# mp3431-led-boost-driver-17mm-mk-1_0_0.net
KiCad netlist of a schematic drawn in EAGLE
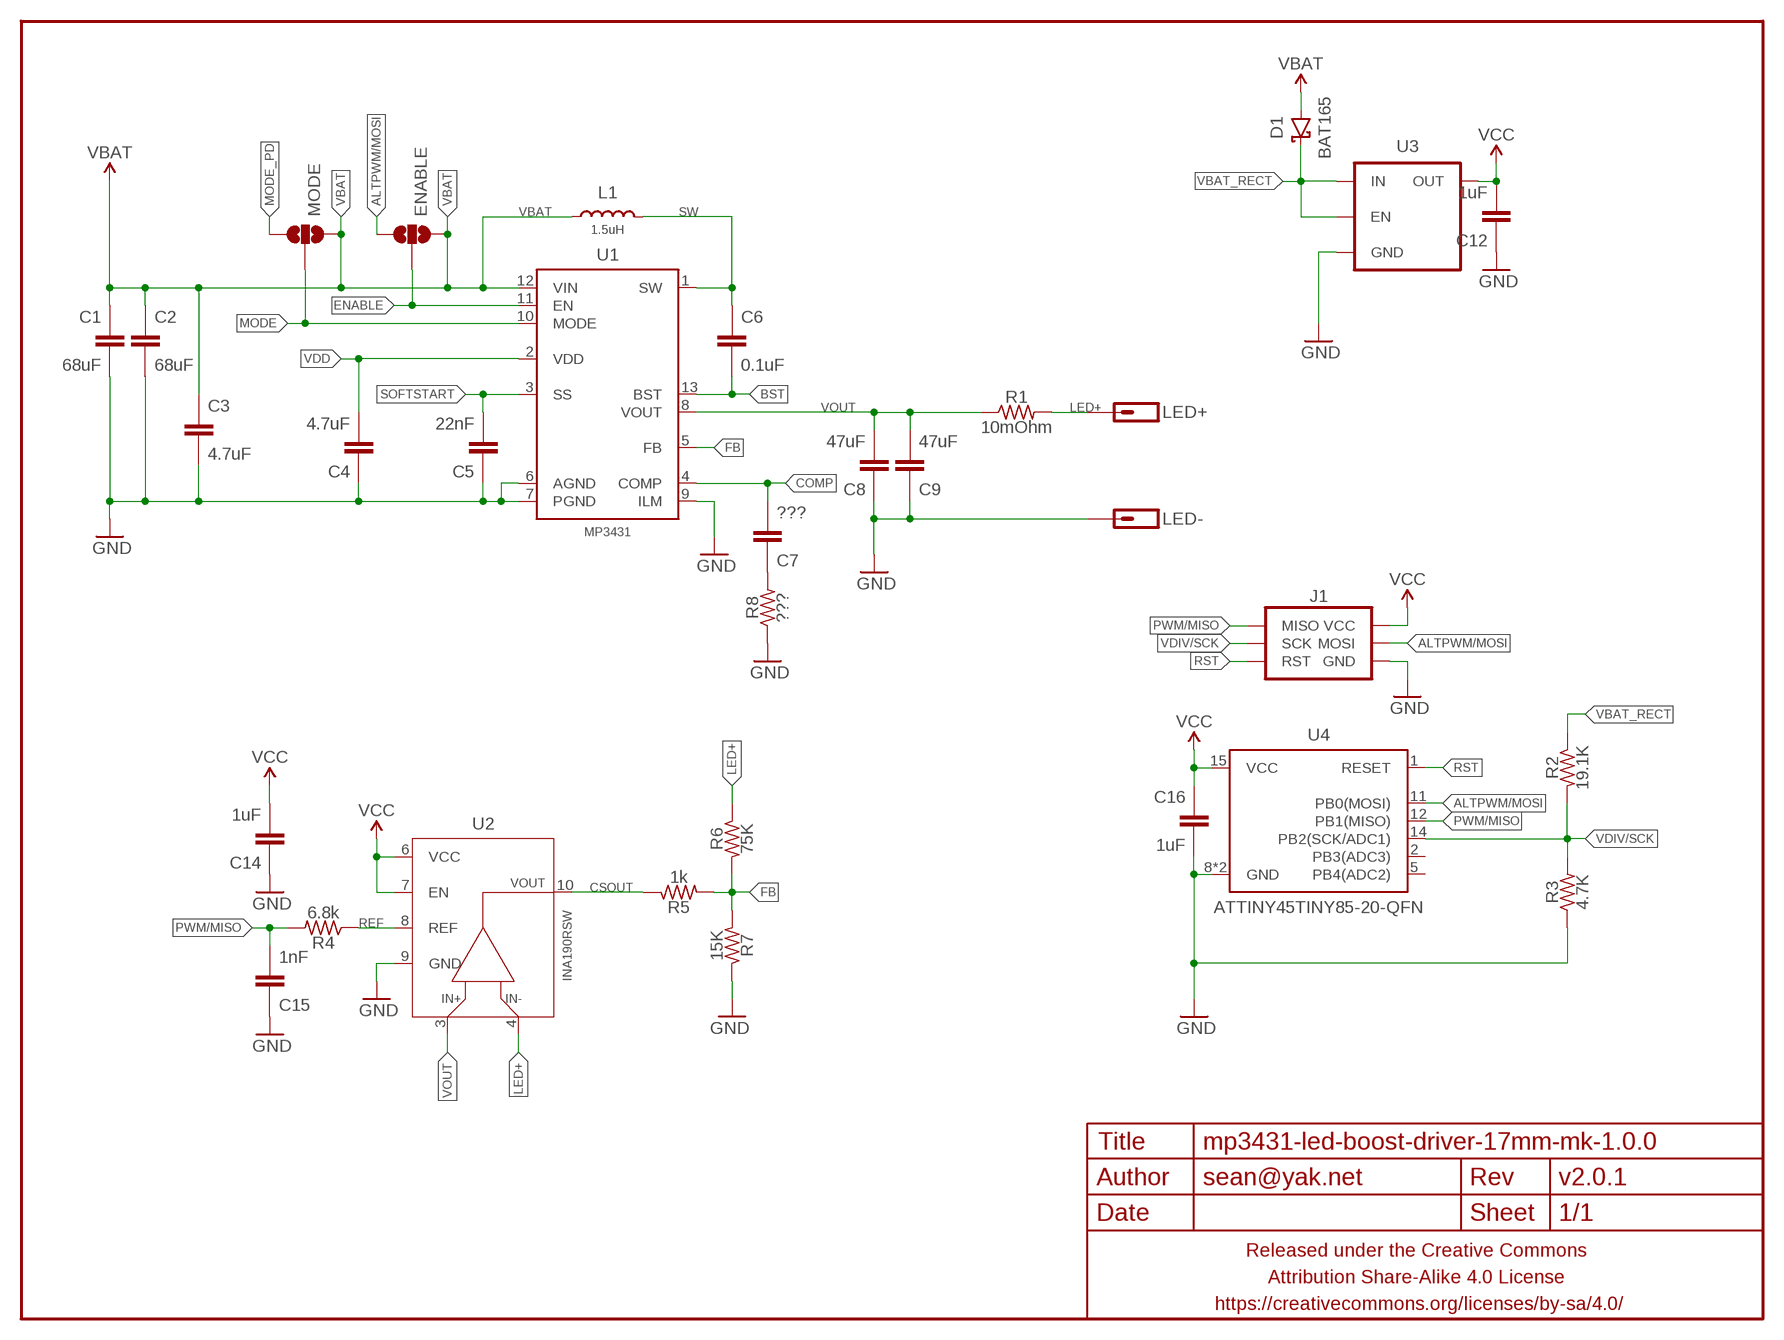
[diagram p0: schematic, sheet 1]

(export (version "E")
  (design (tool "Eeschema 10.0.6"))
  (components
    (comp (ref "C1")
      (value "68uF")
      (footprint "eagle-import:C1206")
      (libsource (lib "eagle-import") (part "CAPACITOR-CERAMICC1206"))
    )
    (comp (ref "C2")
      (value "68uF")
      (footprint "eagle-import:C1206")
      (libsource (lib "eagle-import") (part "CAPACITOR-CERAMICC1206"))
    )
    (comp (ref "C3")
      (value "4.7uF")
      (footprint "eagle-import:C0402")
      (libsource (lib "eagle-import") (part "CAPACITOR-CERAMICC0402"))
    )
    (comp (ref "C4")
      (value "4.7uF")
      (footprint "eagle-import:C0402")
      (libsource (lib "eagle-import") (part "CAPACITOR-CERAMICC0402"))
    )
    (comp (ref "C5")
      (value "22nF")
      (footprint "eagle-import:C0402")
      (libsource (lib "eagle-import") (part "CAPACITOR-CERAMICC0402"))
    )
    (comp (ref "C6")
      (value "0.1uF")
      (footprint "eagle-import:C0402")
      (libsource (lib "eagle-import") (part "CAPACITOR-CERAMICC0402"))
    )
    (comp (ref "C7")
      (value "???")
      (footprint "eagle-import:C0402")
      (libsource (lib "eagle-import") (part "CAPACITOR-CERAMICC0402"))
    )
    (comp (ref "C8")
      (value "47uF")
      (footprint "eagle-import:C1206")
      (libsource (lib "eagle-import") (part "CAPACITOR-CERAMICC1206"))
    )
    (comp (ref "C9")
      (value "47uF")
      (footprint "eagle-import:C1206")
      (libsource (lib "eagle-import") (part "CAPACITOR-CERAMICC1206"))
    )
    (comp (ref "C12")
      (value "1uF")
      (footprint "eagle-import:C0402")
      (libsource (lib "eagle-import") (part "CAPACITOR-CERAMICC0402"))
    )
    (comp (ref "C14")
      (value "1uF")
      (footprint "eagle-import:C0402")
      (libsource (lib "eagle-import") (part "CAPACITOR-CERAMICC0402"))
    )
    (comp (ref "C15")
      (value "1nF")
      (footprint "eagle-import:C0402")
      (libsource (lib "eagle-import") (part "CAPACITOR-CERAMICC0402"))
    )
    (comp (ref "C16")
      (value "1uF")
      (footprint "eagle-import:C0402")
      (libsource (lib "eagle-import") (part "CAPACITOR-CERAMICC0402"))
    )
    (comp (ref "D1")
      (value "BAT165")
      (footprint "eagle-import:SOD323-SCHOTTKY")
      (libsource (lib "eagle-import") (part "DIODE-SCHOTTKYSOD323"))
    )
    (comp (ref "ENABLE")
      (value "JUMPER-PAD-3-NOSMALL_BOX_SILK")
      (footprint "eagle-import:PAD-JUMPER-3-NO_YES_SILK_SMALL_BOX")
      (libsource (lib "eagle-import") (part "JUMPER-PAD-3-NOSMALL_BOX_SILK"))
    )
    (comp (ref "FRAME1")
      (value "FRAME-LETTERNO_PACKAGE")
      (footprint "eagle-import:DUMMY")
      (fields
        (field (name "DESIGNER") "sean@yak.net")
        (field (name "VERSION") "v2.0.1")
        (field (name "DESIGNER_1") "sean@yak.net")
        (field (name "VERSION_1") "v2.0.1")
      )
      (libsource (lib "eagle-import") (part "FRAME-LETTERNO_PACKAGE"))
    )
    (comp (ref "J1")
      (value "AVR_SPI_PRG_6SMD-1.27MM")
      (footprint "eagle-import:2X3-1.27MM-SMD")
      (libsource (lib "eagle-import") (part "AVR_SPI_PRG_6SMD-1.27MM"))
    )
    (comp (ref "L1")
      (value "1.5uH")
      (footprint "eagle-import:XAR7030")
      (libsource (lib "eagle-import") (part "INDUCTORXAR7030"))
    )
    (comp (ref "LED+")
      (value "M01SMD-1.6MMX3.2MM")
      (footprint "eagle-import:1X01-SMD-1.6MMX3.2MM")
      (libsource (lib "eagle-import") (part "M01SMD-1.6MMX3.2MM"))
    )
    (comp (ref "LED-")
      (value "M01SMD-1.6MMX3.2MM")
      (footprint "eagle-import:1X01-SMD-1.6MMX3.2MM")
      (libsource (lib "eagle-import") (part "M01SMD-1.6MMX3.2MM"))
    )
    (comp (ref "MODE")
      (value "JUMPER-PAD-3-NOSMALL_BOX_SILK")
      (footprint "eagle-import:PAD-JUMPER-3-NO_YES_SILK_SMALL_BOX")
      (libsource (lib "eagle-import") (part "JUMPER-PAD-3-NOSMALL_BOX_SILK"))
    )
    (comp (ref "R1")
      (value "10mOhm")
      (footprint "eagle-import:R1206")
      (libsource (lib "eagle-import") (part "RESISTORR1206"))
    )
    (comp (ref "R2")
      (value "19.1K")
      (footprint "eagle-import:R0402")
      (libsource (lib "eagle-import") (part "RESISTORR0402"))
    )
    (comp (ref "R3")
      (value "4.7K")
      (footprint "eagle-import:R0402")
      (libsource (lib "eagle-import") (part "RESISTORR0402"))
    )
    (comp (ref "R4")
      (value "6.8k")
      (footprint "eagle-import:R0402")
      (libsource (lib "eagle-import") (part "RESISTORR0402"))
    )
    (comp (ref "R5")
      (value "1k")
      (footprint "eagle-import:R0402")
      (libsource (lib "eagle-import") (part "RESISTORR0402"))
    )
    (comp (ref "R6")
      (value "75K")
      (footprint "eagle-import:R0402")
      (libsource (lib "eagle-import") (part "RESISTORR0402"))
    )
    (comp (ref "R7")
      (value "15K")
      (footprint "eagle-import:R0402")
      (libsource (lib "eagle-import") (part "RESISTORR0402"))
    )
    (comp (ref "R8")
      (value "???")
      (footprint "eagle-import:R0402")
      (libsource (lib "eagle-import") (part "RESISTORR0402"))
    )
    (comp (ref "U1")
      (value "MP3431")
      (footprint "eagle-import:MP3431")
      (libsource (lib "eagle-import") (part "MP3431"))
    )
    (comp (ref "U2")
      (value "INA190RSW")
      (footprint "eagle-import:UQFN-10")
      (libsource (lib "eagle-import") (part "INA190RSW"))
    )
    (comp (ref "U3")
      (value "V_REG_ENTLV700")
      (footprint "eagle-import:SC70")
      (libsource (lib "eagle-import") (part "V_REG_ENTLV700"))
    )
    (comp (ref "U4")
      (value "ATTINY45TINY85-20-QFN")
      (footprint "eagle-import:QFN20")
      (libsource (lib "eagle-import") (part "ATTINY45TINY85-20-QFN"))
    )
  )
  (nets
    (net (code "1") (name "/CSOUT") (class "Default")
      (node (ref "R5") (pin "1") (pinfunction "1_1") (pintype "passive"))
      (node (ref "U2") (pin "10") (pinfunction "OUT_10") (pintype "bidirectional"))
    )
    (net (code "2") (name "/REF") (class "Default")
      (node (ref "R4") (pin "1") (pinfunction "1_1") (pintype "passive"))
      (node (ref "U2") (pin "8") (pinfunction "REF_8") (pintype "bidirectional"))
    )
    (net (code "3") (name "/SW") (class "Default")
      (node (ref "C6") (pin "1") (pinfunction "1_1") (pintype "passive"))
      (node (ref "L1") (pin "P$2") (pinfunction "2_P$2") (pintype "passive"))
      (node (ref "U1") (pin "1") (pinfunction "SW_1") (pintype "bidirectional"))
    )
    (net (code "4") (name "ALTPWM{slash}MOSI") (class "Default")
      (node (ref "ENABLE") (pin "3") (pinfunction "3_3") (pintype "passive"))
      (node (ref "J1") (pin "4") (pinfunction "MOSI_4") (pintype "passive"))
      (node (ref "U4") (pin "11") (pinfunction "PB0(MOSI)_11") (pintype "bidirectional"))
    )
    (net (code "5") (name "BST") (class "Default")
      (node (ref "C6") (pin "2") (pinfunction "2_2") (pintype "passive"))
      (node (ref "U1") (pin "13") (pinfunction "BST_13") (pintype "bidirectional"))
    )
    (net (code "6") (name "COMP") (class "Default")
      (node (ref "C7") (pin "2") (pinfunction "2_2") (pintype "passive"))
      (node (ref "U1") (pin "4") (pinfunction "COMP_4") (pintype "bidirectional"))
    )
    (net (code "7") (name "ENABLE") (class "Default")
      (node (ref "ENABLE") (pin "2") (pinfunction "2_2") (pintype "passive"))
      (node (ref "U1") (pin "11") (pinfunction "EN_11") (pintype "bidirectional"))
    )
    (net (code "8") (name "FB") (class "Default")
      (node (ref "R5") (pin "2") (pinfunction "2_2") (pintype "passive"))
      (node (ref "R6") (pin "2") (pinfunction "2_2") (pintype "passive"))
      (node (ref "R7") (pin "2") (pinfunction "2_2") (pintype "passive"))
      (node (ref "U1") (pin "5") (pinfunction "FB_5") (pintype "bidirectional"))
    )
    (net (code "9") (name "GND") (class "Default")
      (node (ref "C1") (pin "2") (pinfunction "2_2") (pintype "passive"))
      (node (ref "C12") (pin "1") (pinfunction "1_1") (pintype "passive"))
      (node (ref "C14") (pin "1") (pinfunction "1_1") (pintype "passive"))
      (node (ref "C15") (pin "1") (pinfunction "1_1") (pintype "passive"))
      (node (ref "C16") (pin "2") (pinfunction "2_2") (pintype "passive"))
      (node (ref "C2") (pin "2") (pinfunction "2_2") (pintype "passive"))
      (node (ref "C3") (pin "2") (pinfunction "2_2") (pintype "passive"))
      (node (ref "C4") (pin "1") (pinfunction "1_1") (pintype "passive"))
      (node (ref "C5") (pin "1") (pinfunction "1_1") (pintype "passive"))
      (node (ref "C8") (pin "1") (pinfunction "1_1") (pintype "passive"))
      (node (ref "C9") (pin "1") (pinfunction "1_1") (pintype "passive"))
      (node (ref "J1") (pin "6") (pinfunction "GND_6") (pintype "passive"))
      (node (ref "LED-") (pin "P$1") (pinfunction "1_P$1") (pintype "passive"))
      (node (ref "R3") (pin "1") (pinfunction "1_1") (pintype "passive"))
      (node (ref "R7") (pin "1") (pinfunction "1_1") (pintype "passive"))
      (node (ref "R8") (pin "1") (pinfunction "1_1") (pintype "passive"))
      (node (ref "U1") (pin "6") (pinfunction "AGND_6") (pintype "bidirectional"))
      (node (ref "U1") (pin "7") (pinfunction "PGND_7") (pintype "bidirectional"))
      (node (ref "U1") (pin "9") (pinfunction "ILM_9") (pintype "bidirectional"))
      (node (ref "U2") (pin "9") (pinfunction "GND_9") (pintype "bidirectional"))
      (node (ref "U3") (pin "2") (pinfunction "GND_2") (pintype "input"))
      (node (ref "U4") (pin "8") (pinfunction "GND_8") (pintype "bidirectional"))
      (node (ref "U4") (pin "PAD") (pinfunction "GND_PAD") (pintype "bidirectional"))
    )
    (net (code "10") (name "LED+") (class "Default")
      (node (ref "LED+") (pin "P$1") (pinfunction "1_P$1") (pintype "passive"))
      (node (ref "R1") (pin "2") (pinfunction "2_2") (pintype "passive"))
      (node (ref "R6") (pin "1") (pinfunction "1_1") (pintype "passive"))
      (node (ref "U2") (pin "4") (pinfunction "VIN-_4") (pintype "bidirectional"))
    )
    (net (code "11") (name "MODE") (class "Default")
      (node (ref "MODE") (pin "2") (pinfunction "2_2") (pintype "passive"))
      (node (ref "U1") (pin "10") (pinfunction "MODE_10") (pintype "bidirectional"))
    )
    (net (code "12") (name "MODE_PD") (class "Default")
      (node (ref "MODE") (pin "3") (pinfunction "3_3") (pintype "passive"))
    )
    (net (code "13") (name "Net-(C7-Pad1)") (class "Default")
      (node (ref "C7") (pin "1") (pinfunction "1_1") (pintype "passive"))
      (node (ref "R8") (pin "2") (pinfunction "2_2") (pintype "passive"))
    )
    (net (code "14") (name "PWM{slash}MISO") (class "Default")
      (node (ref "C15") (pin "2") (pinfunction "2_2") (pintype "passive"))
      (node (ref "J1") (pin "1") (pinfunction "MISO_1") (pintype "passive"))
      (node (ref "R4") (pin "2") (pinfunction "2_2") (pintype "passive"))
      (node (ref "U4") (pin "12") (pinfunction "PB1(MISO)_12") (pintype "bidirectional"))
    )
    (net (code "15") (name "RST") (class "Default")
      (node (ref "J1") (pin "5") (pinfunction "RST_5") (pintype "passive"))
      (node (ref "U4") (pin "1") (pinfunction "RESET_1") (pintype "bidirectional"))
    )
    (net (code "16") (name "SOFTSTART") (class "Default")
      (node (ref "C5") (pin "2") (pinfunction "2_2") (pintype "passive"))
      (node (ref "U1") (pin "3") (pinfunction "SS_3") (pintype "bidirectional"))
    )
    (net (code "17") (name "VBAT") (class "Default")
      (node (ref "C1") (pin "1") (pinfunction "1_1") (pintype "passive"))
      (node (ref "C2") (pin "1") (pinfunction "1_1") (pintype "passive"))
      (node (ref "C3") (pin "1") (pinfunction "1_1") (pintype "passive"))
      (node (ref "D1") (pin "A") (pinfunction "A_A") (pintype "passive"))
      (node (ref "ENABLE") (pin "1") (pinfunction "1_1") (pintype "passive"))
      (node (ref "L1") (pin "P$1") (pinfunction "1_P$1") (pintype "passive"))
      (node (ref "MODE") (pin "1") (pinfunction "1_1") (pintype "passive"))
      (node (ref "U1") (pin "12") (pinfunction "VIN_12") (pintype "bidirectional"))
    )
    (net (code "18") (name "VBAT_RECT") (class "Default")
      (node (ref "D1") (pin "C") (pinfunction "C_C") (pintype "passive"))
      (node (ref "R2") (pin "1") (pinfunction "1_1") (pintype "passive"))
      (node (ref "U3") (pin "1") (pinfunction "IN_1") (pintype "input"))
      (node (ref "U3") (pin "3") (pinfunction "EN_3") (pintype "input"))
    )
    (net (code "19") (name "VCC") (class "Default")
      (node (ref "C12") (pin "2") (pinfunction "2_2") (pintype "passive"))
      (node (ref "C14") (pin "2") (pinfunction "2_2") (pintype "passive"))
      (node (ref "C16") (pin "1") (pinfunction "1_1") (pintype "passive"))
      (node (ref "J1") (pin "2") (pinfunction "VCC_2") (pintype "passive"))
      (node (ref "U2") (pin "6") (pinfunction "VCC_6") (pintype "bidirectional"))
      (node (ref "U2") (pin "7") (pinfunction "EN_7") (pintype "bidirectional"))
      (node (ref "U3") (pin "5") (pinfunction "OUT_5") (pintype "passive"))
      (node (ref "U4") (pin "15") (pinfunction "VCC_15") (pintype "bidirectional"))
    )
    (net (code "20") (name "VDD") (class "Default")
      (node (ref "C4") (pin "2") (pinfunction "2_2") (pintype "passive"))
      (node (ref "U1") (pin "2") (pinfunction "VDD_2") (pintype "bidirectional"))
    )
    (net (code "21") (name "VDIV{slash}SCK") (class "Default")
      (node (ref "J1") (pin "3") (pinfunction "SCK_3") (pintype "passive"))
      (node (ref "R2") (pin "2") (pinfunction "2_2") (pintype "passive"))
      (node (ref "R3") (pin "2") (pinfunction "2_2") (pintype "passive"))
      (node (ref "U4") (pin "14") (pinfunction "PB2(SCK/ADC1)_14") (pintype "bidirectional"))
    )
    (net (code "22") (name "VOUT") (class "Default")
      (node (ref "C8") (pin "2") (pinfunction "2_2") (pintype "passive"))
      (node (ref "C9") (pin "2") (pinfunction "2_2") (pintype "passive"))
      (node (ref "R1") (pin "1") (pinfunction "1_1") (pintype "passive"))
      (node (ref "U1") (pin "8") (pinfunction "VOUT_8") (pintype "bidirectional"))
      (node (ref "U2") (pin "3") (pinfunction "VIN+_3") (pintype "bidirectional"))
    )
    (net (code "23") (name "unconnected-(U4-PB3(ADC3)-Pad2)") (class "Default")
      (node (ref "U4") (pin "2") (pinfunction "PB3(ADC3)_2") (pintype "bidirectional"))
    )
    (net (code "24") (name "unconnected-(U4-PB4(ADC2)-Pad5)") (class "Default")
      (node (ref "U4") (pin "5") (pinfunction "PB4(ADC2)_5") (pintype "bidirectional"))
    )
  )
)
